# lightbox_circuit.net
KiCad netlist of a schematic drawn in EAGLE
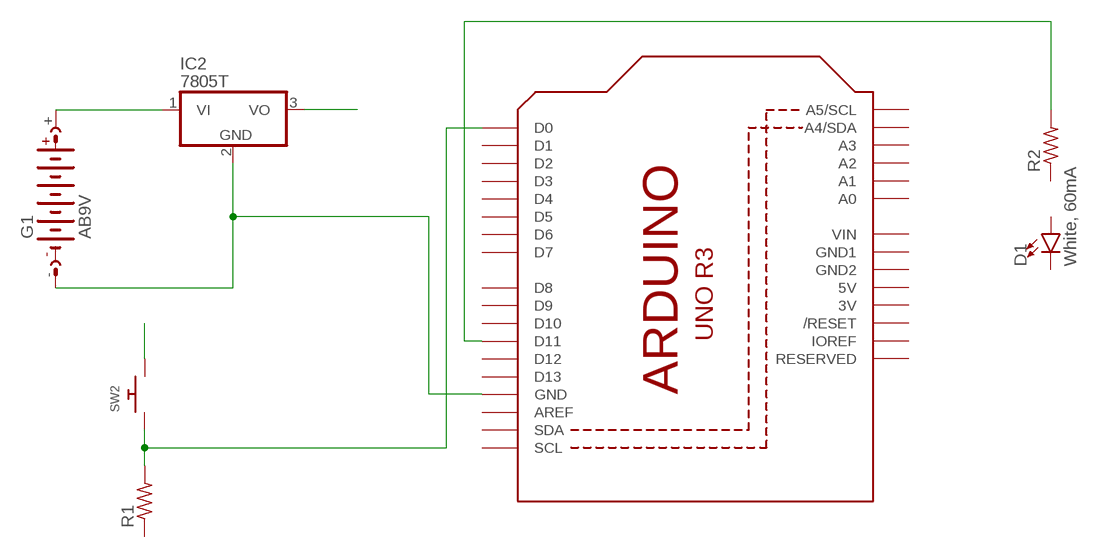
[diagram p0: schematic, sheet 1]

(export (version "E")
  (design (tool "Eeschema 10.0.6"))
  (components
    (comp (ref "D1")
      (value "White, 60mA")
      (footprint "eagle-import:SUPER_BRIGHT_SMD_LED_3014")
      (libsource (lib "eagle-import") (part "LED-WHITE3014"))
    )
    (comp (ref "G1")
      (value "AB9V")
      (footprint "eagle-import:AB9V")
      (libsource (lib "eagle-import") (part "AB9V"))
    )
    (comp (ref "IC2")
      (value "7805T")
      (footprint "eagle-import:TO220H")
      (libsource (lib "eagle-import") (part "78T05"))
    )
    (comp (ref "R1")
      (value "R-US_0414/15")
      (footprint "eagle-import:0414_15")
      (libsource (lib "eagle-import") (part "R-US_0414/15"))
    )
    (comp (ref "R2")
      (value "R-US_0414/15")
      (footprint "eagle-import:0414_15")
      (libsource (lib "eagle-import") (part "R-US_0414/15"))
    )
    (comp (ref "SW2")
      (value "SWITCH_PUSHBUTTONSOFTTOUCHSMD_SJ")
      (footprint "eagle-import:PUSHBUTTON_SMD_SJ")
      (libsource (lib "eagle-import") (part "SWITCH_PUSHBUTTONSOFTTOUCHSMD_SJ"))
    )
    (comp (ref "U1")
      (value "ARDUINOR3-DIMENSION")
      (footprint "eagle-import:ARDUINOR3")
      (libsource (lib "eagle-import") (part "ARDUINOR3-DIMENSION"))
    )
  )
  (nets
    (net (code "1") (name "/3V") (class "Default")
      (node (ref "U1") (pin "3V") (pinfunction "3V_3V") (pintype "power_in"))
    )
    (net (code "2") (name "/5V") (class "Default")
      (node (ref "U1") (pin "5V") (pinfunction "5V_5V") (pintype "power_in"))
    )
    (net (code "3") (name "/GND1") (class "Default")
      (node (ref "U1") (pin "GND1") (pinfunction "GND1_GND1") (pintype "power_in"))
    )
    (net (code "4") (name "/GND2") (class "Default")
      (node (ref "U1") (pin "GND2") (pinfunction "GND2_GND2") (pintype "power_in"))
    )
    (net (code "5") (name "/VIN") (class "Default")
      (node (ref "U1") (pin "VIN") (pinfunction "VIN_VIN") (pintype "power_in"))
    )
    (net (code "6") (name "Net-(IC2-GND)") (class "Default")
      (node (ref "G1") (pin "-") (pinfunction "-_-") (pintype "passive"))
      (node (ref "IC2") (pin "2") (pinfunction "GND_2") (pintype "passive"))
      (node (ref "U1") (pin "GND") (pinfunction "GND_GND") (pintype "power_in"))
    )
    (net (code "7") (name "Net-(IC2-VI)") (class "Default")
      (node (ref "G1") (pin "+") (pinfunction "+_+") (pintype "passive"))
      (node (ref "IC2") (pin "1") (pinfunction "VI_1") (pintype "input"))
    )
    (net (code "8") (name "Net-(R1-Pad2)") (class "Default")
      (node (ref "R1") (pin "2") (pinfunction "2_2") (pintype "passive"))
      (node (ref "SW2") (pin "P$1") (pinfunction "P$1_P$1") (pintype "passive"))
      (node (ref "U1") (pin "D0") (pinfunction "D0_D0") (pintype "bidirectional"))
    )
    (net (code "9") (name "Net-(R2-Pad2)") (class "Default")
      (node (ref "R2") (pin "2") (pinfunction "2_2") (pintype "passive"))
      (node (ref "U1") (pin "D11") (pinfunction "D11_D11") (pintype "bidirectional"))
    )
    (net (code "10") (name "unconnected-(D1-PadA)") (class "Default")
      (node (ref "D1") (pin "A") (pinfunction "A_A") (pintype "passive"))
    )
    (net (code "11") (name "unconnected-(D1-PadC)") (class "Default")
      (node (ref "D1") (pin "C") (pinfunction "C_C") (pintype "passive"))
    )
    (net (code "12") (name "unconnected-(IC2-VO-Pad3)") (class "Default")
      (node (ref "IC2") (pin "3") (pinfunction "VO_3") (pintype "passive"))
    )
    (net (code "13") (name "unconnected-(R1-Pad1)") (class "Default")
      (node (ref "R1") (pin "1") (pinfunction "1_1") (pintype "passive"))
    )
    (net (code "14") (name "unconnected-(R2-Pad1)") (class "Default")
      (node (ref "R2") (pin "1") (pinfunction "1_1") (pintype "passive"))
    )
    (net (code "15") (name "unconnected-(SW2-PadP$2)") (class "Default")
      (node (ref "SW2") (pin "P$2") (pinfunction "P$2_P$2") (pintype "passive"))
    )
    (net (code "16") (name "unconnected-(U1-A4{slash}SDA-PadA4)") (class "Default")
      (node (ref "U1") (pin "A4") (pinfunction "A4/SDA_A4") (pintype "bidirectional"))
    )
    (net (code "17") (name "unconnected-(U1-A5{slash}SCL-PadA5)") (class "Default")
      (node (ref "U1") (pin "A5") (pinfunction "A5/SCL_A5") (pintype "bidirectional"))
    )
    (net (code "18") (name "unconnected-(U1-PadA0)") (class "Default")
      (node (ref "U1") (pin "A0") (pinfunction "A0_A0") (pintype "bidirectional"))
    )
    (net (code "19") (name "unconnected-(U1-PadA1)") (class "Default")
      (node (ref "U1") (pin "A1") (pinfunction "A1_A1") (pintype "bidirectional"))
    )
    (net (code "20") (name "unconnected-(U1-PadA2)") (class "Default")
      (node (ref "U1") (pin "A2") (pinfunction "A2_A2") (pintype "bidirectional"))
    )
    (net (code "21") (name "unconnected-(U1-PadA3)") (class "Default")
      (node (ref "U1") (pin "A3") (pinfunction "A3_A3") (pintype "bidirectional"))
    )
    (net (code "22") (name "unconnected-(U1-PadAREF)") (class "Default")
      (node (ref "U1") (pin "AREF") (pinfunction "AREF_AREF") (pintype "bidirectional"))
    )
    (net (code "23") (name "unconnected-(U1-PadD1)") (class "Default")
      (node (ref "U1") (pin "D1") (pinfunction "D1_D1") (pintype "bidirectional"))
    )
    (net (code "24") (name "unconnected-(U1-PadD2)") (class "Default")
      (node (ref "U1") (pin "D2") (pinfunction "D2_D2") (pintype "bidirectional"))
    )
    (net (code "25") (name "unconnected-(U1-PadD3)") (class "Default")
      (node (ref "U1") (pin "D3") (pinfunction "D3_D3") (pintype "bidirectional"))
    )
    (net (code "26") (name "unconnected-(U1-PadD4)") (class "Default")
      (node (ref "U1") (pin "D4") (pinfunction "D4_D4") (pintype "bidirectional"))
    )
    (net (code "27") (name "unconnected-(U1-PadD5)") (class "Default")
      (node (ref "U1") (pin "D5") (pinfunction "D5_D5") (pintype "bidirectional"))
    )
    (net (code "28") (name "unconnected-(U1-PadD6)") (class "Default")
      (node (ref "U1") (pin "D6") (pinfunction "D6_D6") (pintype "bidirectional"))
    )
    (net (code "29") (name "unconnected-(U1-PadD7)") (class "Default")
      (node (ref "U1") (pin "D7") (pinfunction "D7_D7") (pintype "bidirectional"))
    )
    (net (code "30") (name "unconnected-(U1-PadD8)") (class "Default")
      (node (ref "U1") (pin "D8") (pinfunction "D8_D8") (pintype "bidirectional"))
    )
    (net (code "31") (name "unconnected-(U1-PadD9)") (class "Default")
      (node (ref "U1") (pin "D9") (pinfunction "D9_D9") (pintype "bidirectional"))
    )
    (net (code "32") (name "unconnected-(U1-PadD10)") (class "Default")
      (node (ref "U1") (pin "D10") (pinfunction "D10_D10") (pintype "bidirectional"))
    )
    (net (code "33") (name "unconnected-(U1-PadD12)") (class "Default")
      (node (ref "U1") (pin "D12") (pinfunction "D12_D12") (pintype "bidirectional"))
    )
    (net (code "34") (name "unconnected-(U1-PadD13)") (class "Default")
      (node (ref "U1") (pin "D13") (pinfunction "D13_D13") (pintype "bidirectional"))
    )
    (net (code "35") (name "unconnected-(U1-PadIOREF)") (class "Default")
      (node (ref "U1") (pin "IOREF") (pinfunction "IOREF_IOREF") (pintype "output"))
    )
    (net (code "36") (name "unconnected-(U1-PadRESERVED)") (class "Default")
      (node (ref "U1") (pin "RESERVED") (pinfunction "RESERVED_RESERVED") (pintype "no_connect"))
    )
    (net (code "37") (name "unconnected-(U1-PadSCL)") (class "Default")
      (node (ref "U1") (pin "SCL") (pinfunction "SCL_SCL") (pintype "bidirectional"))
    )
    (net (code "38") (name "unconnected-(U1-PadSDA)") (class "Default")
      (node (ref "U1") (pin "SDA") (pinfunction "SDA_SDA") (pintype "bidirectional"))
    )
    (net (code "39") (name "unconnected-(U1-{slash}RESET-PadRESET)") (class "Default")
      (node (ref "U1") (pin "RESET") (pinfunction "/RESET_RESET") (pintype "bidirectional"))
    )
  )
)
